# DashHubV5.net
KiCad netlist of a schematic drawn in EAGLE
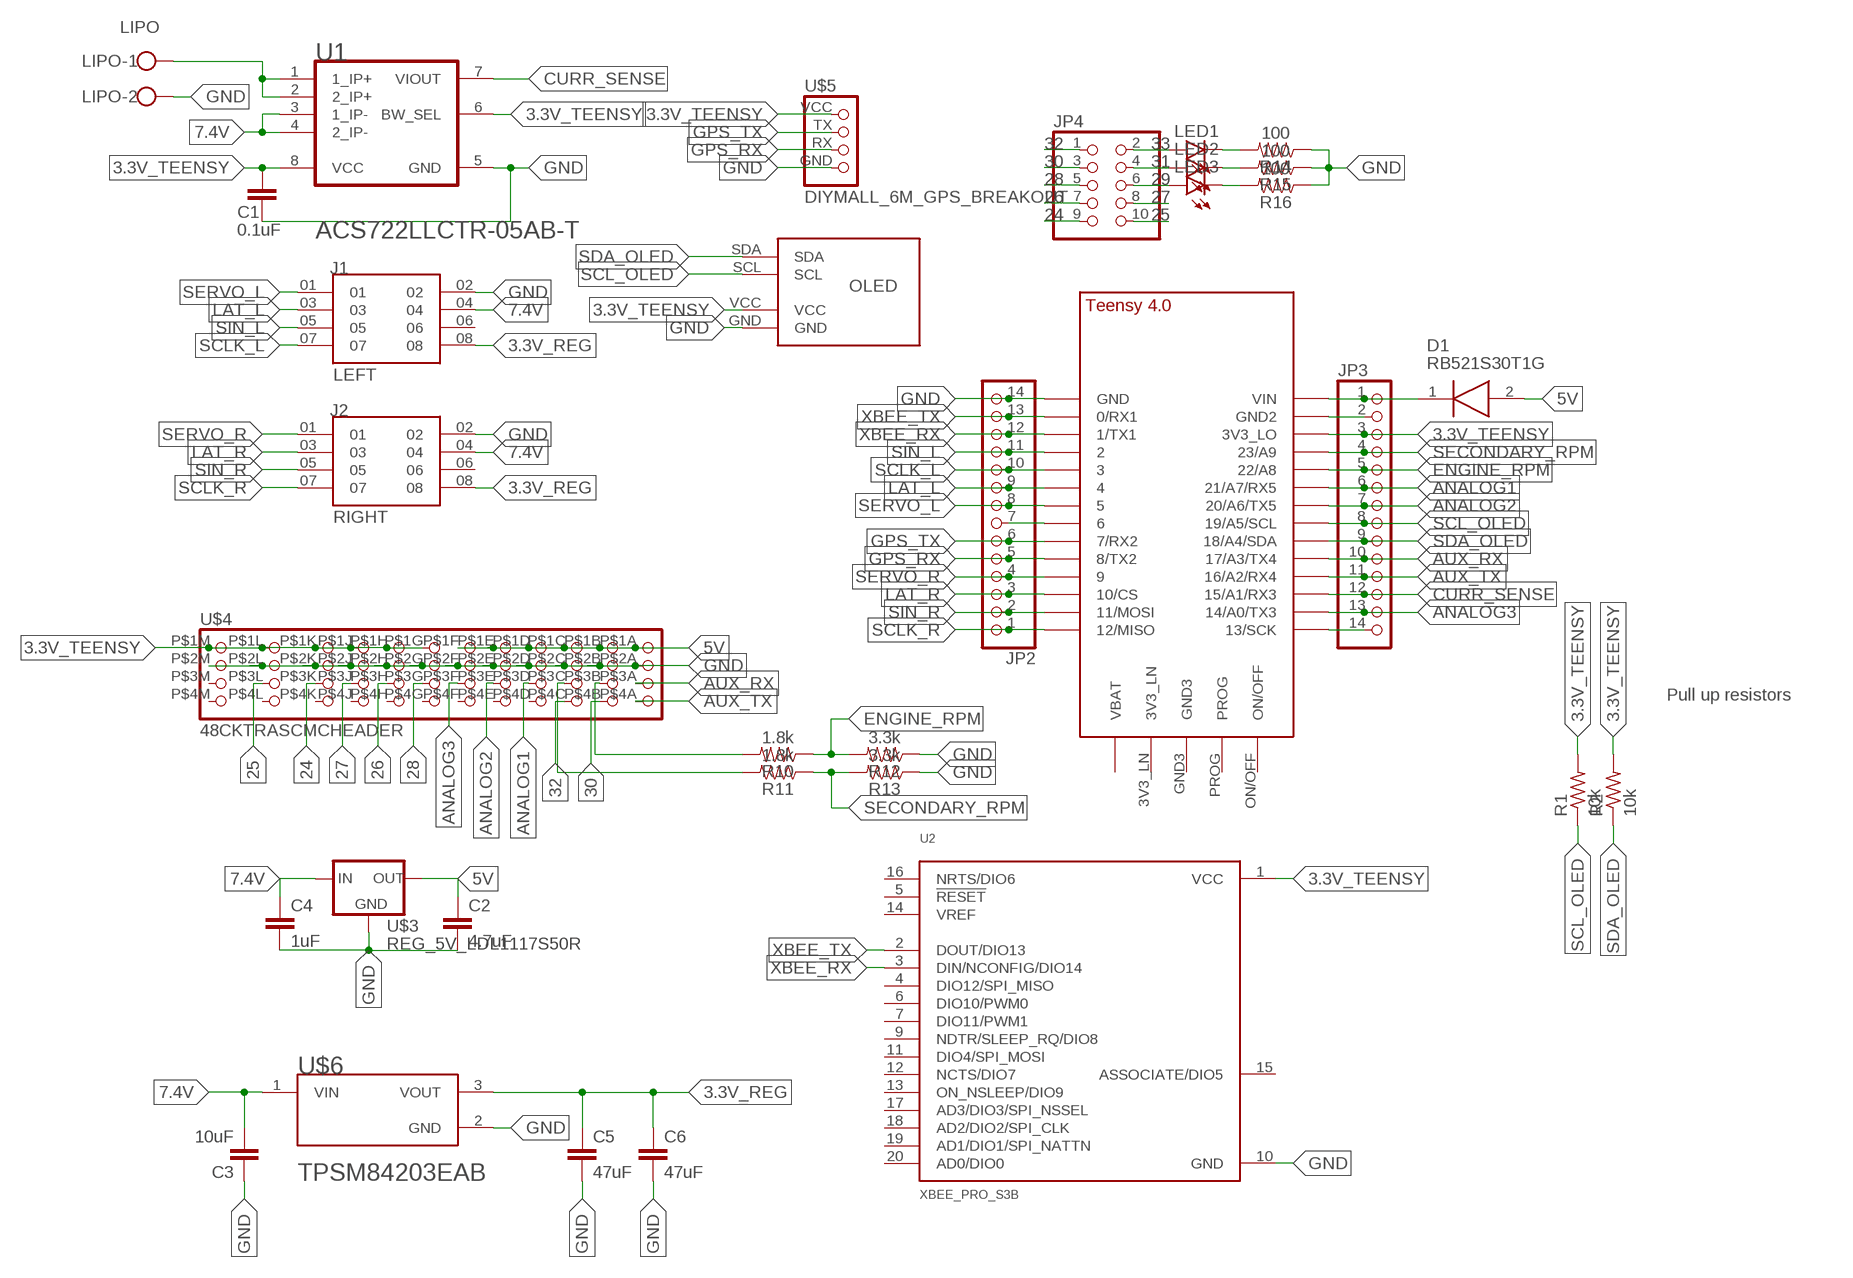
[diagram p0: schematic, sheet 1]

(export (version "E")
  (design (tool "Eeschema 10.0.6"))
  (components
    (comp (ref "C1")
      (value "0.1uF")
      (footprint "eagle-import:C0402")
      (libsource (lib "eagle-import") (part "C-EUC0402"))
    )
    (comp (ref "C2")
      (value "4.7uF")
      (footprint "eagle-import:C0603")
      (libsource (lib "eagle-import") (part "CAP_SMDC0603"))
    )
    (comp (ref "C3")
      (value "10uF")
      (footprint "eagle-import:C1206")
      (libsource (lib "eagle-import") (part "CAP_SMDC1206"))
    )
    (comp (ref "C4")
      (value "1uF")
      (footprint "eagle-import:C1206")
      (libsource (lib "eagle-import") (part "CAP_SMDC1206"))
    )
    (comp (ref "C5")
      (value "47uF")
      (footprint "eagle-import:C1206")
      (libsource (lib "eagle-import") (part "CAP_SMDC1206"))
    )
    (comp (ref "C6")
      (value "47uF")
      (footprint "eagle-import:C1206")
      (libsource (lib "eagle-import") (part "CAP_SMDC1206"))
    )
    (comp (ref "D1")
      (value "RB521S30T1G")
      (footprint "eagle-import:SODFL1608X70N")
      (fields (field (name "MOUSER_PART_NUMBER") "863-RB521S30T1G"))
      (libsource (lib "eagle-import") (part "RB521S30T1G"))
    )
    (comp (ref "J1")
      (value "LEFT")
      (footprint "eagle-import:SAMTEC_ESW-104-23-L-D")
      (fields (field (name "MANUFACTURER") "Samtec Inc."))
      (libsource (lib "eagle-import") (part "ESW-104-23-L-D"))
    )
    (comp (ref "J2")
      (value "RIGHT")
      (footprint "eagle-import:SAMTEC_ESW-104-23-L-D")
      (fields (field (name "MANUFACTURER") "Samtec Inc."))
      (libsource (lib "eagle-import") (part "ESW-104-23-L-D"))
    )
    (comp (ref "JP2")
      (value "PINHD-1X14")
      (footprint "eagle-import:1X14")
      (libsource (lib "eagle-import") (part "PINHD-1X14"))
    )
    (comp (ref "JP3")
      (value "PINHD-1X14")
      (footprint "eagle-import:1X14")
      (libsource (lib "eagle-import") (part "PINHD-1X14"))
    )
    (comp (ref "JP4")
      (value "PINHD-2X5")
      (footprint "eagle-import:2X05")
      (libsource (lib "eagle-import") (part "PINHD-2X5"))
    )
    (comp (ref "LED1")
      (value "LEDCHIPLED_1206")
      (footprint "eagle-import:CHIPLED_1206")
      (libsource (lib "eagle-import") (part "LEDCHIPLED_1206"))
    )
    (comp (ref "LED2")
      (value "LEDCHIPLED_1206")
      (footprint "eagle-import:CHIPLED_1206")
      (libsource (lib "eagle-import") (part "LEDCHIPLED_1206"))
    )
    (comp (ref "LED3")
      (value "LEDCHIPLED_1206")
      (footprint "eagle-import:CHIPLED_1206")
      (libsource (lib "eagle-import") (part "LEDCHIPLED_1206"))
    )
    (comp (ref "LIPO")
      (value "LIPO")
      (footprint "eagle-import:W237-102")
      (fields (field (name "MPN") "237-102"))
      (libsource (lib "eagle-import") (part "W237-102"))
    )
    (comp (ref "R1")
      (value "10k")
      (footprint "eagle-import:R0603")
      (libsource (lib "eagle-import") (part "RES_SMDR0603"))
    )
    (comp (ref "R2")
      (value "10k")
      (footprint "eagle-import:R0603")
      (libsource (lib "eagle-import") (part "RES_SMDR0603"))
    )
    (comp (ref "R10")
      (value "1.8k")
      (footprint "eagle-import:AXIAL-0.3")
      (libsource (lib "eagle-import") (part "RESISTORAXIAL-0.3"))
    )
    (comp (ref "R11")
      (value "1.8k")
      (footprint "eagle-import:AXIAL-0.3")
      (libsource (lib "eagle-import") (part "RESISTORAXIAL-0.3"))
    )
    (comp (ref "R12")
      (value "3.3k")
      (footprint "eagle-import:AXIAL-0.3")
      (libsource (lib "eagle-import") (part "RESISTORAXIAL-0.3"))
    )
    (comp (ref "R13")
      (value "3.3k")
      (footprint "eagle-import:AXIAL-0.3")
      (libsource (lib "eagle-import") (part "RESISTORAXIAL-0.3"))
    )
    (comp (ref "R14")
      (value "100")
      (footprint "eagle-import:AXIAL-0.3")
      (libsource (lib "eagle-import") (part "RESISTORAXIAL-0.3"))
    )
    (comp (ref "R15")
      (value "100")
      (footprint "eagle-import:AXIAL-0.3")
      (libsource (lib "eagle-import") (part "RESISTORAXIAL-0.3"))
    )
    (comp (ref "R16")
      (value "100")
      (footprint "eagle-import:AXIAL-0.3")
      (libsource (lib "eagle-import") (part "RESISTORAXIAL-0.3"))
    )
    (comp (ref "U$1")
      (value "TEENSY_4.0-BASIC")
      (footprint "eagle-import:TEENSY_4.0-BASIC")
      (libsource (lib "eagle-import") (part "TEENSY_4.0-BASIC"))
    )
    (comp (ref "U$2")
      (value "OLED_SSD1306")
      (footprint "eagle-import:OLED_SSD1306")
      (libsource (lib "eagle-import") (part "OLED_SSD1306"))
    )
    (comp (ref "U$3")
      (value "REG_5V_LDL1117S50R")
      (footprint "eagle-import:SOT230P700X180-4N")
      (libsource (lib "eagle-import") (part "REG_5V_LDL1117S50R"))
    )
    (comp (ref "U$4")
      (value "48CKTRASCMCHEADER")
      (footprint "eagle-import:48CKTRASCMCHEADER")
      (libsource (lib "eagle-import") (part "48CKTRASCMCHEADER"))
    )
    (comp (ref "U$5")
      (value "DIYMALL_6M_GPS_BREAKOUT")
      (footprint "eagle-import:DIYMALL_6M_GPS_BREAKOUT")
      (libsource (lib "eagle-import") (part "DIYMALL_6M_GPS_BREAKOUT"))
    )
    (comp (ref "U$6")
      (value "TPSM84205EAB")
      (footprint "eagle-import:TPSM84205EAB")
      (libsource (lib "eagle-import") (part "TPSM84205EAB"))
    )
    (comp (ref "U1")
      (value "ALLEGRO_MICROSYSTEMS_ACS722LLCTR-05AB-TALLEGRO_MICROSYSTEMS_ACS722LLCTR-05AB-T_0_0")
      (footprint "eagle-import:ALLEGRO_MICROSYSTEMS_ACS722LLCTR-05AB-T_0")
      (fields (field (name "MF") "Allegro MicroSystems") (field (name "MPN") "ACS722LLCTR-05AB-T"))
      (libsource (lib "eagle-import") (part "ALLEGRO_MICROSYSTEMS_ACS722LLCTR-05AB-TALLEGRO_MICROSYSTEMS_ACS722LLCTR-05AB-T_0_0"))
    )
    (comp (ref "U2")
      (value "XBEE_PRO_S3B")
      (footprint "eagle-import:XBEE_PRO_S3B")
      (fields
        (field (name "DIGI-KEY_PART_NUMBER") "602-1293-ND")
        (field (name "MF") "Digi International")
        (field (name "MP") "XBP9B-XCST-001")
      )
      (libsource (lib "eagle-import") (part "XBEE_PRO_S3B"))
    )
  )
  (nets
    (net (code "1") (name "/29") (class "Default")
      (node (ref "JP4") (pin "6") (pinfunction "6_6") (pintype "passive"))
      (node (ref "LED3") (pin "A") (pinfunction "A_A") (pintype "passive"))
    )
    (net (code "2") (name "/31") (class "Default")
      (node (ref "JP4") (pin "4") (pinfunction "4_4") (pintype "passive"))
      (node (ref "LED2") (pin "A") (pinfunction "A_A") (pintype "passive"))
    )
    (net (code "3") (name "/33") (class "Default")
      (node (ref "JP4") (pin "2") (pinfunction "2_2") (pintype "passive"))
      (node (ref "LED1") (pin "A") (pinfunction "A_A") (pintype "passive"))
    )
    (net (code "4") (name "3.3V_REG") (class "Default")
      (node (ref "C5") (pin "1") (pinfunction "1_1") (pintype "passive"))
      (node (ref "C6") (pin "1") (pinfunction "1_1") (pintype "passive"))
      (node (ref "J1") (pin "08") (pinfunction "08_08") (pintype "passive"))
      (node (ref "J2") (pin "08") (pinfunction "08_08") (pintype "passive"))
      (node (ref "U$6") (pin "3") (pinfunction "VOUT_3") (pintype "power_in"))
    )
    (net (code "5") (name "3.3V_TEENSY") (class "Default")
      (node (ref "C1") (pin "2") (pinfunction "2_2") (pintype "passive"))
      (node (ref "JP3") (pin "3") (pinfunction "3_3") (pintype "passive"))
      (node (ref "R1") (pin "2") (pinfunction "2_2") (pintype "passive"))
      (node (ref "R2") (pin "2") (pinfunction "2_2") (pintype "passive"))
      (node (ref "U$1") (pin "3V3_LO") (pinfunction "3V3_LO_3V3_LO") (pintype "bidirectional"))
      (node (ref "U$2") (pin "VCC") (pinfunction "VCC_VCC") (pintype "bidirectional"))
      (node (ref "U$4") (pin "P$1G") (pinfunction "1G_P$1G") (pintype "passive"))
      (node (ref "U$4") (pin "P$1H") (pinfunction "1H_P$1H") (pintype "passive"))
      (node (ref "U$4") (pin "P$1J") (pinfunction "1J_P$1J") (pintype "passive"))
      (node (ref "U$4") (pin "P$1K") (pinfunction "1K_P$1K") (pintype "passive"))
      (node (ref "U$4") (pin "P$1L") (pinfunction "1L_P$1L") (pintype "passive"))
      (node (ref "U$4") (pin "P$1M") (pinfunction "1M_P$1M") (pintype "passive"))
      (node (ref "U$5") (pin "VCC") (pinfunction "VCC_VCC") (pintype "passive"))
      (node (ref "U1") (pin "6") (pinfunction "BW_SEL_6") (pintype "input"))
      (node (ref "U1") (pin "8") (pinfunction "VCC_8") (pintype "power_in"))
      (node (ref "U2") (pin "1") (pinfunction "VCC_1") (pintype "power_in"))
    )
    (net (code "6") (name "5V") (class "Default")
      (node (ref "C2") (pin "1") (pinfunction "1_1") (pintype "passive"))
      (node (ref "D1") (pin "2") (pinfunction "A_2") (pintype "bidirectional"))
      (node (ref "U$3") (pin "2") (pinfunction "OUT_2") (pintype "output"))
      (node (ref "U$3") (pin "4") (pinfunction "OUT_4") (pintype "output"))
      (node (ref "U$4") (pin "P$1A") (pinfunction "1A_P$1A") (pintype "passive"))
      (node (ref "U$4") (pin "P$1B") (pinfunction "1B_P$1B") (pintype "passive"))
      (node (ref "U$4") (pin "P$1C") (pinfunction "1C_P$1C") (pintype "passive"))
      (node (ref "U$4") (pin "P$1D") (pinfunction "1D_P$1D") (pintype "passive"))
      (node (ref "U$4") (pin "P$1E") (pinfunction "1E_P$1E") (pintype "passive"))
      (node (ref "U$4") (pin "P$1F") (pinfunction "1F_P$1F") (pintype "passive"))
    )
    (net (code "7") (name "7.4V") (class "Default")
      (node (ref "C3") (pin "2") (pinfunction "2_2") (pintype "passive"))
      (node (ref "C4") (pin "1") (pinfunction "1_1") (pintype "passive"))
      (node (ref "J1") (pin "04") (pinfunction "04_04") (pintype "passive"))
      (node (ref "J2") (pin "04") (pinfunction "04_04") (pintype "passive"))
      (node (ref "U$3") (pin "3") (pinfunction "IN_3") (pintype "input"))
      (node (ref "U$6") (pin "1") (pinfunction "VIN_1") (pintype "power_in"))
      (node (ref "U1") (pin "3") (pinfunction "1_IP-_3") (pintype "input"))
      (node (ref "U1") (pin "4") (pinfunction "2_IP-_4") (pintype "input"))
    )
    (net (code "8") (name "24") (class "Default")
      (node (ref "JP4") (pin "9") (pinfunction "9_9") (pintype "passive"))
      (node (ref "U$4") (pin "P$3K") (pinfunction "3K_P$3K") (pintype "passive"))
    )
    (net (code "9") (name "25") (class "Default")
      (node (ref "JP4") (pin "10") (pinfunction "10_10") (pintype "passive"))
      (node (ref "U$4") (pin "P$3L") (pinfunction "3L_P$3L") (pintype "passive"))
    )
    (net (code "10") (name "26") (class "Default")
      (node (ref "JP4") (pin "7") (pinfunction "7_7") (pintype "passive"))
      (node (ref "U$4") (pin "P$3H") (pinfunction "3H_P$3H") (pintype "passive"))
    )
    (net (code "11") (name "27") (class "Default")
      (node (ref "JP4") (pin "8") (pinfunction "8_8") (pintype "passive"))
      (node (ref "U$4") (pin "P$3J") (pinfunction "3J_P$3J") (pintype "passive"))
    )
    (net (code "12") (name "28") (class "Default")
      (node (ref "JP4") (pin "5") (pinfunction "5_5") (pintype "passive"))
      (node (ref "U$4") (pin "P$3G") (pinfunction "3G_P$3G") (pintype "passive"))
    )
    (net (code "13") (name "30") (class "Default")
      (node (ref "JP4") (pin "3") (pinfunction "3_3") (pintype "passive"))
      (node (ref "U$4") (pin "P$4B") (pinfunction "4B_P$4B") (pintype "passive"))
    )
    (net (code "14") (name "32") (class "Default")
      (node (ref "JP4") (pin "1") (pinfunction "1_1") (pintype "passive"))
      (node (ref "U$4") (pin "P$4C") (pinfunction "4C_P$4C") (pintype "passive"))
    )
    (net (code "15") (name "ANALOG1") (class "Default")
      (node (ref "JP3") (pin "6") (pinfunction "6_6") (pintype "passive"))
      (node (ref "U$1") (pin "21/A7") (pinfunction "21/A7/RX5_21/A7") (pintype "bidirectional"))
      (node (ref "U$4") (pin "P$3D") (pinfunction "3D_P$3D") (pintype "passive"))
    )
    (net (code "16") (name "ANALOG2") (class "Default")
      (node (ref "JP3") (pin "7") (pinfunction "7_7") (pintype "passive"))
      (node (ref "U$1") (pin "20/A6") (pinfunction "20/A6/TX5_20/A6") (pintype "bidirectional"))
      (node (ref "U$4") (pin "P$3E") (pinfunction "3E_P$3E") (pintype "passive"))
    )
    (net (code "17") (name "ANALOG3") (class "Default")
      (node (ref "JP3") (pin "13") (pinfunction "13_13") (pintype "passive"))
      (node (ref "U$1") (pin "14/A0") (pinfunction "14/A0/TX3_14/A0") (pintype "bidirectional"))
      (node (ref "U$4") (pin "P$3F") (pinfunction "3F_P$3F") (pintype "passive"))
    )
    (net (code "18") (name "AUX_RX") (class "Default")
      (node (ref "JP3") (pin "10") (pinfunction "10_10") (pintype "passive"))
      (node (ref "U$1") (pin "17/A3") (pinfunction "17/A3/TX4_17/A3") (pintype "bidirectional"))
      (node (ref "U$4") (pin "P$3A") (pinfunction "3A_P$3A") (pintype "passive"))
    )
    (net (code "19") (name "AUX_TX") (class "Default")
      (node (ref "JP3") (pin "11") (pinfunction "11_11") (pintype "passive"))
      (node (ref "U$1") (pin "16/A2") (pinfunction "16/A2/RX4_16/A2") (pintype "bidirectional"))
      (node (ref "U$4") (pin "P$4A") (pinfunction "4A_P$4A") (pintype "passive"))
    )
    (net (code "20") (name "CURR_SENSE") (class "Default")
      (node (ref "JP3") (pin "12") (pinfunction "12_12") (pintype "passive"))
      (node (ref "U$1") (pin "15/A1") (pinfunction "15/A1/RX3_15/A1") (pintype "bidirectional"))
      (node (ref "U1") (pin "7") (pinfunction "VIOUT_7") (pintype "output"))
    )
    (net (code "21") (name "ENGINE_RPM") (class "Default")
      (node (ref "JP3") (pin "5") (pinfunction "5_5") (pintype "passive"))
      (node (ref "R10") (pin "P$1") (pinfunction "1_P$1") (pintype "passive"))
      (node (ref "R12") (pin "P$2") (pinfunction "2_P$2") (pintype "passive"))
      (node (ref "U$1") (pin "22/A8") (pinfunction "22/A8_22/A8") (pintype "bidirectional"))
    )
    (net (code "22") (name "GND") (class "Default")
      (node (ref "C1") (pin "1") (pinfunction "1_1") (pintype "passive"))
      (node (ref "C2") (pin "2") (pinfunction "2_2") (pintype "passive"))
      (node (ref "C3") (pin "1") (pinfunction "1_1") (pintype "passive"))
      (node (ref "C4") (pin "2") (pinfunction "2_2") (pintype "passive"))
      (node (ref "C5") (pin "2") (pinfunction "2_2") (pintype "passive"))
      (node (ref "C6") (pin "2") (pinfunction "2_2") (pintype "passive"))
      (node (ref "J1") (pin "02") (pinfunction "02_02") (pintype "passive"))
      (node (ref "J2") (pin "02") (pinfunction "02_02") (pintype "passive"))
      (node (ref "JP2") (pin "14") (pinfunction "14_14") (pintype "passive"))
      (node (ref "LIPO") (pin "2") (pinfunction "KL_2") (pintype "passive"))
      (node (ref "R12") (pin "P$1") (pinfunction "1_P$1") (pintype "passive"))
      (node (ref "R13") (pin "P$1") (pinfunction "1_P$1") (pintype "passive"))
      (node (ref "R14") (pin "P$1") (pinfunction "1_P$1") (pintype "passive"))
      (node (ref "R15") (pin "P$1") (pinfunction "1_P$1") (pintype "passive"))
      (node (ref "R16") (pin "P$1") (pinfunction "1_P$1") (pintype "passive"))
      (node (ref "U$1") (pin "GND") (pinfunction "GND_GND") (pintype "bidirectional"))
      (node (ref "U$2") (pin "GND") (pinfunction "GND_GND") (pintype "bidirectional"))
      (node (ref "U$3") (pin "1") (pinfunction "GND_1") (pintype "input"))
      (node (ref "U$4") (pin "P$2A") (pinfunction "2A_P$2A") (pintype "passive"))
      (node (ref "U$4") (pin "P$2B") (pinfunction "2B_P$2B") (pintype "passive"))
      (node (ref "U$4") (pin "P$2C") (pinfunction "2C_P$2C") (pintype "passive"))
      (node (ref "U$4") (pin "P$2D") (pinfunction "2D_P$2D") (pintype "passive"))
      (node (ref "U$4") (pin "P$2E") (pinfunction "2E_P$2E") (pintype "passive"))
      (node (ref "U$4") (pin "P$2F") (pinfunction "2F_P$2F") (pintype "passive"))
      (node (ref "U$4") (pin "P$2G") (pinfunction "2G_P$2G") (pintype "passive"))
      (node (ref "U$4") (pin "P$2H") (pinfunction "2H_P$2H") (pintype "passive"))
      (node (ref "U$4") (pin "P$2J") (pinfunction "2J_P$2J") (pintype "passive"))
      (node (ref "U$4") (pin "P$2K") (pinfunction "2K_P$2K") (pintype "passive"))
      (node (ref "U$4") (pin "P$2L") (pinfunction "2L_P$2L") (pintype "passive"))
      (node (ref "U$4") (pin "P$2M") (pinfunction "2M_P$2M") (pintype "passive"))
      (node (ref "U$5") (pin "GND") (pinfunction "GND_GND") (pintype "passive"))
      (node (ref "U$6") (pin "2") (pinfunction "GND_2") (pintype "power_in"))
      (node (ref "U1") (pin "5") (pinfunction "GND_5") (pintype "power_in"))
      (node (ref "U2") (pin "10") (pinfunction "GND_10") (pintype "power_in"))
    )
    (net (code "23") (name "GPS_RX") (class "Default")
      (node (ref "JP2") (pin "5") (pinfunction "5_5") (pintype "passive"))
      (node (ref "U$1") (pin "8") (pinfunction "8/TX2_8") (pintype "bidirectional"))
      (node (ref "U$5") (pin "RX") (pinfunction "RX_RX") (pintype "passive"))
    )
    (net (code "24") (name "GPS_TX") (class "Default")
      (node (ref "JP2") (pin "6") (pinfunction "6_6") (pintype "passive"))
      (node (ref "U$1") (pin "7") (pinfunction "7/RX2_7") (pintype "bidirectional"))
      (node (ref "U$5") (pin "TX") (pinfunction "TX_TX") (pintype "passive"))
    )
    (net (code "25") (name "LAT_L") (class "Default")
      (node (ref "J1") (pin "03") (pinfunction "03_03") (pintype "passive"))
      (node (ref "JP2") (pin "9") (pinfunction "9_9") (pintype "passive"))
      (node (ref "U$1") (pin "4/CANRX") (pinfunction "4_4/CANRX") (pintype "bidirectional"))
    )
    (net (code "26") (name "LAT_R") (class "Default")
      (node (ref "J2") (pin "03") (pinfunction "03_03") (pintype "passive"))
      (node (ref "JP2") (pin "3") (pinfunction "3_3") (pintype "passive"))
      (node (ref "U$1") (pin "10/CS") (pinfunction "10/CS_10/CS") (pintype "bidirectional"))
    )
    (net (code "27") (name "Net-(D1-K)") (class "Default")
      (node (ref "D1") (pin "1") (pinfunction "K_1") (pintype "bidirectional"))
      (node (ref "JP3") (pin "1") (pinfunction "1_1") (pintype "passive"))
      (node (ref "U$1") (pin "VIN") (pinfunction "VIN_VIN") (pintype "bidirectional"))
    )
    (net (code "28") (name "Net-(JP2-Pad7)") (class "Default")
      (node (ref "JP2") (pin "7") (pinfunction "7_7") (pintype "passive"))
      (node (ref "U$1") (pin "6") (pinfunction "6_6") (pintype "bidirectional"))
    )
    (net (code "29") (name "Net-(JP3-Pad2)") (class "Default")
      (node (ref "JP3") (pin "2") (pinfunction "2_2") (pintype "passive"))
      (node (ref "U$1") (pin "GND2") (pinfunction "GND2_GND2") (pintype "bidirectional"))
    )
    (net (code "30") (name "Net-(JP3-Pad14)") (class "Default")
      (node (ref "JP3") (pin "14") (pinfunction "14_14") (pintype "passive"))
      (node (ref "U$1") (pin "13/SCK") (pinfunction "13/SCK_13/SCK") (pintype "bidirectional"))
    )
    (net (code "31") (name "Net-(LIPOA-KL)") (class "Default")
      (node (ref "LIPO") (pin "1") (pinfunction "KL_1") (pintype "passive"))
      (node (ref "U1") (pin "1") (pinfunction "1_IP+_1") (pintype "input"))
      (node (ref "U1") (pin "2") (pinfunction "2_IP+_2") (pintype "input"))
    )
    (net (code "32") (name "Net-(R10-2)") (class "Default")
      (node (ref "R10") (pin "P$2") (pinfunction "2_P$2") (pintype "passive"))
      (node (ref "U$4") (pin "P$3B") (pinfunction "3B_P$3B") (pintype "passive"))
    )
    (net (code "33") (name "Net-(R11-2)") (class "Default")
      (node (ref "R11") (pin "P$2") (pinfunction "2_P$2") (pintype "passive"))
      (node (ref "U$4") (pin "P$3C") (pinfunction "3C_P$3C") (pintype "passive"))
    )
    (net (code "34") (name "Net-(R14-2)") (class "Default")
      (node (ref "LED1") (pin "C") (pinfunction "C_C") (pintype "passive"))
      (node (ref "R14") (pin "P$2") (pinfunction "2_P$2") (pintype "passive"))
    )
    (net (code "35") (name "Net-(R15-2)") (class "Default")
      (node (ref "LED2") (pin "C") (pinfunction "C_C") (pintype "passive"))
      (node (ref "R15") (pin "P$2") (pinfunction "2_P$2") (pintype "passive"))
    )
    (net (code "36") (name "Net-(R16-2)") (class "Default")
      (node (ref "LED3") (pin "C") (pinfunction "C_C") (pintype "passive"))
      (node (ref "R16") (pin "P$2") (pinfunction "2_P$2") (pintype "passive"))
    )
    (net (code "37") (name "SCLK_L") (class "Default")
      (node (ref "J1") (pin "07") (pinfunction "07_07") (pintype "passive"))
      (node (ref "JP2") (pin "10") (pinfunction "10_10") (pintype "passive"))
      (node (ref "U$1") (pin "3/CANTX") (pinfunction "3_3/CANTX") (pintype "bidirectional"))
    )
    (net (code "38") (name "SCLK_R") (class "Default")
      (node (ref "J2") (pin "07") (pinfunction "07_07") (pintype "passive"))
      (node (ref "JP2") (pin "1") (pinfunction "1_1") (pintype "passive"))
      (node (ref "U$1") (pin "12/MISO") (pinfunction "12/MISO_12/MISO") (pintype "bidirectional"))
    )
    (net (code "39") (name "SCL_OLED") (class "Default")
      (node (ref "JP3") (pin "8") (pinfunction "8_8") (pintype "passive"))
      (node (ref "R1") (pin "1") (pinfunction "1_1") (pintype "passive"))
      (node (ref "U$1") (pin "19/A5/SCL") (pinfunction "19/A5/SCL_19/A5/SCL") (pintype "bidirectional"))
      (node (ref "U$2") (pin "SCL") (pinfunction "SCL_SCL") (pintype "bidirectional"))
    )
    (net (code "40") (name "SDA_OLED") (class "Default")
      (node (ref "JP3") (pin "9") (pinfunction "9_9") (pintype "passive"))
      (node (ref "R2") (pin "1") (pinfunction "1_1") (pintype "passive"))
      (node (ref "U$1") (pin "18/A4/SDA") (pinfunction "18/A4/SDA_18/A4/SDA") (pintype "bidirectional"))
      (node (ref "U$2") (pin "SDA") (pinfunction "SDA_SDA") (pintype "bidirectional"))
    )
    (net (code "41") (name "SECONDARY_RPM") (class "Default")
      (node (ref "JP3") (pin "4") (pinfunction "4_4") (pintype "passive"))
      (node (ref "R11") (pin "P$1") (pinfunction "1_P$1") (pintype "passive"))
      (node (ref "R13") (pin "P$2") (pinfunction "2_P$2") (pintype "passive"))
      (node (ref "U$1") (pin "23/A9") (pinfunction "23/A9_23/A9") (pintype "bidirectional"))
    )
    (net (code "42") (name "SERVO_L") (class "Default")
      (node (ref "J1") (pin "01") (pinfunction "01_01") (pintype "passive"))
      (node (ref "JP2") (pin "8") (pinfunction "8_8") (pintype "passive"))
      (node (ref "U$1") (pin "5") (pinfunction "5_5") (pintype "bidirectional"))
    )
    (net (code "43") (name "SERVO_R") (class "Default")
      (node (ref "J2") (pin "01") (pinfunction "01_01") (pintype "passive"))
      (node (ref "JP2") (pin "4") (pinfunction "4_4") (pintype "passive"))
      (node (ref "U$1") (pin "9/CS") (pinfunction "9_9/CS") (pintype "bidirectional"))
    )
    (net (code "44") (name "SIN_L") (class "Default")
      (node (ref "J1") (pin "05") (pinfunction "05_05") (pintype "passive"))
      (node (ref "JP2") (pin "11") (pinfunction "11_11") (pintype "passive"))
      (node (ref "U$1") (pin "2") (pinfunction "2_2") (pintype "bidirectional"))
    )
    (net (code "45") (name "SIN_R") (class "Default")
      (node (ref "J2") (pin "05") (pinfunction "05_05") (pintype "passive"))
      (node (ref "JP2") (pin "2") (pinfunction "2_2") (pintype "passive"))
      (node (ref "U$1") (pin "11/MOSI") (pinfunction "11/MOSI_11/MOSI") (pintype "bidirectional"))
    )
    (net (code "46") (name "XBEE_RX") (class "Default")
      (node (ref "JP2") (pin "12") (pinfunction "12_12") (pintype "passive"))
      (node (ref "U$1") (pin "1/TX") (pinfunction "1/TX1_1/TX") (pintype "bidirectional"))
      (node (ref "U2") (pin "3") (pinfunction "DIN/NCONFIG/DIO14_3") (pintype "bidirectional"))
    )
    (net (code "47") (name "XBEE_TX") (class "Default")
      (node (ref "JP2") (pin "13") (pinfunction "13_13") (pintype "passive"))
      (node (ref "U$1") (pin "0/RX") (pinfunction "0/RX1_0/RX") (pintype "bidirectional"))
      (node (ref "U2") (pin "2") (pinfunction "DOUT/DIO13_2") (pintype "bidirectional"))
    )
    (net (code "48") (name "unconnected-(J1-Pad06)") (class "Default")
      (node (ref "J1") (pin "06") (pinfunction "06_06") (pintype "passive"))
    )
    (net (code "49") (name "unconnected-(J2-Pad06)") (class "Default")
      (node (ref "J2") (pin "06") (pinfunction "06_06") (pintype "passive"))
    )
    (net (code "50") (name "unconnected-(U$1-Pad3V3_LN)") (class "Default")
      (node (ref "U$1") (pin "3V3_LN") (pinfunction "3V3_LN_3V3_LN") (pintype "bidirectional"))
    )
    (net (code "51") (name "unconnected-(U$1-PadGND3)") (class "Default")
      (node (ref "U$1") (pin "GND3") (pinfunction "GND3_GND3") (pintype "bidirectional"))
    )
    (net (code "52") (name "unconnected-(U$1-PadON{slash}OFF)") (class "Default")
      (node (ref "U$1") (pin "ON/OFF") (pinfunction "ON/OFF_ON/OFF") (pintype "bidirectional"))
    )
    (net (code "53") (name "unconnected-(U$1-PadPROG)") (class "Default")
      (node (ref "U$1") (pin "PROG") (pinfunction "PROG_PROG") (pintype "bidirectional"))
    )
    (net (code "54") (name "unconnected-(U$1-VBAT-PadVBAT\\)") (class "Default")
      (node (ref "U$1") (pin "VBAT\\") (pinfunction "VBAT_VBAT\\") (pintype "bidirectional"))
    )
    (net (code "55") (name "unconnected-(U$4-3M-PadP$3M)") (class "Default")
      (node (ref "U$4") (pin "P$3M") (pinfunction "3M_P$3M") (pintype "passive"))
    )
    (net (code "56") (name "unconnected-(U$4-4D-PadP$4D)") (class "Default")
      (node (ref "U$4") (pin "P$4D") (pinfunction "4D_P$4D") (pintype "passive"))
    )
    (net (code "57") (name "unconnected-(U$4-4E-PadP$4E)") (class "Default")
      (node (ref "U$4") (pin "P$4E") (pinfunction "4E_P$4E") (pintype "passive"))
    )
    (net (code "58") (name "unconnected-(U$4-4F-PadP$4F)") (class "Default")
      (node (ref "U$4") (pin "P$4F") (pinfunction "4F_P$4F") (pintype "passive"))
    )
    (net (code "59") (name "unconnected-(U$4-4G-PadP$4G)") (class "Default")
      (node (ref "U$4") (pin "P$4G") (pinfunction "4G_P$4G") (pintype "passive"))
    )
    (net (code "60") (name "unconnected-(U$4-4H-PadP$4H)") (class "Default")
      (node (ref "U$4") (pin "P$4H") (pinfunction "4H_P$4H") (pintype "passive"))
    )
    (net (code "61") (name "unconnected-(U$4-4J-PadP$4J)") (class "Default")
      (node (ref "U$4") (pin "P$4J") (pinfunction "4J_P$4J") (pintype "passive"))
    )
    (net (code "62") (name "unconnected-(U$4-4K-PadP$4K)") (class "Default")
      (node (ref "U$4") (pin "P$4K") (pinfunction "4K_P$4K") (pintype "passive"))
    )
    (net (code "63") (name "unconnected-(U$4-4L-PadP$4L)") (class "Default")
      (node (ref "U$4") (pin "P$4L") (pinfunction "4L_P$4L") (pintype "passive"))
    )
    (net (code "64") (name "unconnected-(U$4-4M-PadP$4M)") (class "Default")
      (node (ref "U$4") (pin "P$4M") (pinfunction "4M_P$4M") (pintype "passive"))
    )
    (net (code "65") (name "unconnected-(U2-AD0{slash}DIO0-Pad20)") (class "Default")
      (node (ref "U2") (pin "20") (pinfunction "AD0/DIO0_20") (pintype "bidirectional"))
    )
    (net (code "66") (name "unconnected-(U2-AD1{slash}DIO1{slash}SPI_NATTN-Pad19)") (class "Default")
      (node (ref "U2") (pin "19") (pinfunction "AD1/DIO1/SPI_NATTN_19") (pintype "bidirectional"))
    )
    (net (code "67") (name "unconnected-(U2-AD2{slash}DIO2{slash}SPI_CLK-Pad18)") (class "Default")
      (node (ref "U2") (pin "18") (pinfunction "AD2/DIO2/SPI_CLK_18") (pintype "bidirectional"))
    )
    (net (code "68") (name "unconnected-(U2-AD3{slash}DIO3{slash}SPI_NSSEL-Pad17)") (class "Default")
      (node (ref "U2") (pin "17") (pinfunction "AD3/DIO3/SPI_NSSEL_17") (pintype "bidirectional"))
    )
    (net (code "69") (name "unconnected-(U2-ASSOCIATE{slash}DIO5-Pad15)") (class "Default")
      (node (ref "U2") (pin "15") (pinfunction "ASSOCIATE/DIO5_15") (pintype "output"))
    )
    (net (code "70") (name "unconnected-(U2-DIO4{slash}SPI_MOSI-Pad11)") (class "Default")
      (node (ref "U2") (pin "11") (pinfunction "DIO4/SPI_MOSI_11") (pintype "bidirectional"))
    )
    (net (code "71") (name "unconnected-(U2-DIO10{slash}PWM0-Pad6)") (class "Default")
      (node (ref "U2") (pin "6") (pinfunction "DIO10/PWM0_6") (pintype "bidirectional"))
    )
    (net (code "72") (name "unconnected-(U2-DIO11{slash}PWM1-Pad7)") (class "Default")
      (node (ref "U2") (pin "7") (pinfunction "DIO11/PWM1_7") (pintype "bidirectional"))
    )
    (net (code "73") (name "unconnected-(U2-DIO12{slash}SPI_MISO-Pad4)") (class "Default")
      (node (ref "U2") (pin "4") (pinfunction "DIO12/SPI_MISO_4") (pintype "bidirectional"))
    )
    (net (code "74") (name "unconnected-(U2-NCTS{slash}DIO7-Pad12)") (class "Default")
      (node (ref "U2") (pin "12") (pinfunction "NCTS/DIO7_12") (pintype "bidirectional"))
    )
    (net (code "75") (name "unconnected-(U2-NDTR{slash}SLEEP_RQ{slash}DIO8-Pad9)") (class "Default")
      (node (ref "U2") (pin "9") (pinfunction "NDTR/SLEEP_RQ/DIO8_9") (pintype "bidirectional"))
    )
    (net (code "76") (name "unconnected-(U2-NRTS{slash}DIO6-Pad16)") (class "Default")
      (node (ref "U2") (pin "16") (pinfunction "NRTS/DIO6_16") (pintype "input"))
    )
    (net (code "77") (name "unconnected-(U2-ON_NSLEEP{slash}DIO9-Pad13)") (class "Default")
      (node (ref "U2") (pin "13") (pinfunction "ON_NSLEEP/DIO9_13") (pintype "bidirectional"))
    )
    (net (code "78") (name "unconnected-(U2-VREF-Pad14)") (class "Default")
      (node (ref "U2") (pin "14") (pinfunction "VREF_14") (pintype "input"))
    )
    (net (code "79") (name "unconnected-(U2-~{RESET}-Pad5)") (class "Default")
      (node (ref "U2") (pin "5") (pinfunction "~{RESET}_5") (pintype "input"))
    )
  )
)
